# lightningbug.net
KiCad netlist of a schematic drawn in EAGLE
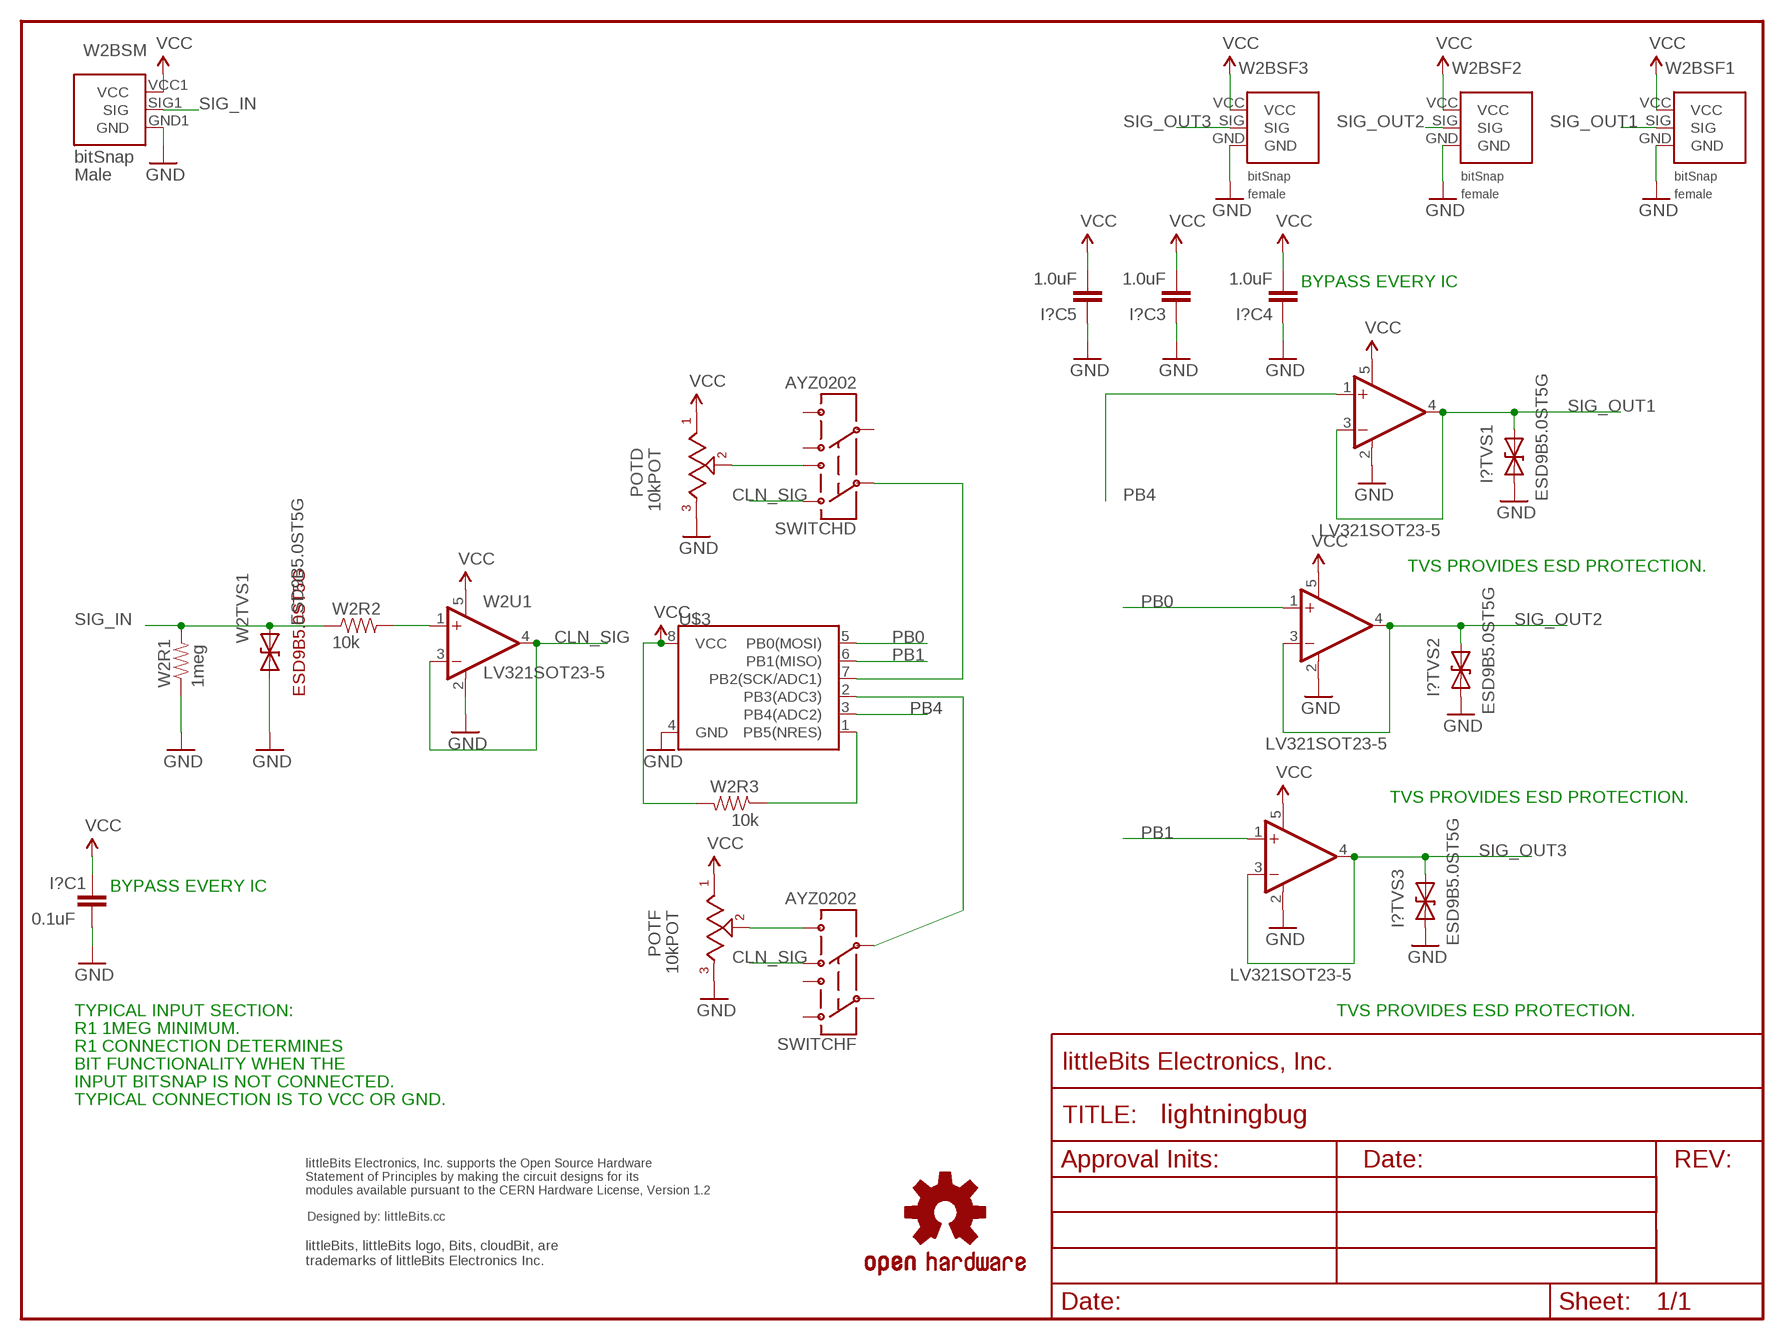
[diagram p0: schematic, sheet 1]

(export (version "E")
  (design (tool "Eeschema 10.0.6"))
  (components
    (comp (ref "FRAME1")
      (value "FRAME-LETTER")
      (footprint "eagle-import:FABDWG01-OHW")
      (libsource (lib "eagle-import") (part "FRAME-LETTER"))
    )
    (comp (ref "I?C1")
      (value "0.1uF")
      (footprint "eagle-import:CAP-0603")
      (libsource (lib "eagle-import") (part "CAPCAP-0603"))
    )
    (comp (ref "I?C3")
      (value "1.0uF")
      (footprint "eagle-import:CAP-0603")
      (libsource (lib "eagle-import") (part "CAPCAP-0603"))
    )
    (comp (ref "I?C4")
      (value "1.0uF")
      (footprint "eagle-import:CAP-0603")
      (libsource (lib "eagle-import") (part "CAPCAP-0603"))
    )
    (comp (ref "I?C5")
      (value "1.0uF")
      (footprint "eagle-import:CAP-0603")
      (libsource (lib "eagle-import") (part "CAPCAP-0603"))
    )
    (comp (ref "I?TVS1")
      (value "ESD9B5.0ST5G")
      (footprint "eagle-import:SOD-923")
      (libsource (lib "eagle-import") (part "DIODE-TVSSOD-923"))
    )
    (comp (ref "I?TVS2")
      (value "ESD9B5.0ST5G")
      (footprint "eagle-import:SOD-923")
      (libsource (lib "eagle-import") (part "DIODE-TVSSOD-923"))
    )
    (comp (ref "I?TVS3")
      (value "ESD9B5.0ST5G")
      (footprint "eagle-import:SOD-923")
      (libsource (lib "eagle-import") (part "DIODE-TVSSOD-923"))
    )
    (comp (ref "POTD")
      (value "10kPOT")
      (footprint "eagle-import:TRIMPOT_SMD_3MM")
      (libsource (lib "eagle-import") (part "TRIMPOT_SMD_3MM"))
    )
    (comp (ref "POTF")
      (value "10kPOT")
      (footprint "eagle-import:TRIMPOT_SMD_3MM")
      (libsource (lib "eagle-import") (part "TRIMPOT_SMD_3MM"))
    )
    (comp (ref "SWITCHD")
      (value "AYZ0202")
      (footprint "eagle-import:AYZ0202")
      (libsource (lib "eagle-import") (part "AYZ0202"))
    )
    (comp (ref "SWITCHF")
      (value "AYZ0202")
      (footprint "eagle-import:AYZ0202")
      (libsource (lib "eagle-import") (part "AYZ0202"))
    )
    (comp (ref "U$1")
      (value "OSHWCREDIT")
      (footprint "eagle-import:OSHWCREDIT")
      (libsource (lib "eagle-import") (part "OSHWCREDIT"))
    )
    (comp (ref "U$3")
      (value "ATTINY85")
      (footprint "eagle-import:SO08-EIAJ")
      (libsource (lib "eagle-import") (part "ATTINY85"))
    )
    (comp (ref "U$6")
      (value "OSHW-LOGOL")
      (footprint "eagle-import:OSHW-LOGO-L")
      (libsource (lib "eagle-import") (part "OSHW-LOGOL"))
    )
    (comp (ref "U1")
      (value "LV321SOT23-5")
      (footprint "eagle-import:SOT23-5")
      (libsource (lib "eagle-import") (part "LV321SOT23-5"))
    )
    (comp (ref "U2")
      (value "LV321SOT23-5")
      (footprint "eagle-import:SOT23-5")
      (libsource (lib "eagle-import") (part "LV321SOT23-5"))
    )
    (comp (ref "U3")
      (value "LV321SOT23-5")
      (footprint "eagle-import:SOT23-5")
      (libsource (lib "eagle-import") (part "LV321SOT23-5"))
    )
    (comp (ref "W2BSF1")
      (value "BITSNAP_V03_FEMALE")
      (footprint "eagle-import:BITSNAP_V03_FEMALE")
      (libsource (lib "eagle-import") (part "BITSNAP_V03_FEMALE"))
    )
    (comp (ref "W2BSF2")
      (value "BITSNAP_V03_FEMALE")
      (footprint "eagle-import:BITSNAP_V03_FEMALE")
      (libsource (lib "eagle-import") (part "BITSNAP_V03_FEMALE"))
    )
    (comp (ref "W2BSF3")
      (value "BITSNAP_V03_FEMALE")
      (footprint "eagle-import:BITSNAP_V03_FEMALE")
      (libsource (lib "eagle-import") (part "BITSNAP_V03_FEMALE"))
    )
    (comp (ref "W2BSM")
      (value "BITSNAP_V03_MALE")
      (footprint "eagle-import:BITSNAP_V03_MALE")
      (libsource (lib "eagle-import") (part "BITSNAP_V03_MALE"))
    )
    (comp (ref "W2R1")
      (value "1meg")
      (footprint "eagle-import:RES-0603")
      (libsource (lib "eagle-import") (part "RESISTOR0603"))
    )
    (comp (ref "W2R2")
      (value "10k")
      (footprint "eagle-import:RES-0603")
      (libsource (lib "eagle-import") (part "RESISTOR0603"))
    )
    (comp (ref "W2R3")
      (value "10k")
      (footprint "eagle-import:RES-0603")
      (libsource (lib "eagle-import") (part "RES-0603"))
    )
    (comp (ref "W2TVS1")
      (value "ESD9B5.0ST5G")
      (footprint "eagle-import:SOD-923")
      (libsource (lib "eagle-import") (part "DIODE-TVSSOD-923"))
    )
    (comp (ref "W2U1")
      (value "LV321SOT23-5")
      (footprint "eagle-import:SOT23-5")
      (libsource (lib "eagle-import") (part "LV321SOT23-5"))
    )
  )
  (nets
    (net (code "1") (name "/CLN_SIG") (class "Default")
      (node (ref "SWITCHD") (pin "1") (pinfunction "1_1") (pintype "bidirectional"))
      (node (ref "SWITCHF") (pin "4") (pinfunction "4_4") (pintype "bidirectional"))
      (node (ref "W2U1") (pin "3") (pinfunction "-IN_3") (pintype "input"))
      (node (ref "W2U1") (pin "4") (pinfunction "OUT_4") (pintype "output"))
    )
    (net (code "2") (name "/PB0") (class "Default")
      (node (ref "U$3") (pin "5") (pinfunction "PB0(MOSI)_5") (pintype "bidirectional"))
      (node (ref "U2") (pin "1") (pinfunction "+IN_1") (pintype "input"))
    )
    (net (code "3") (name "/PB1") (class "Default")
      (node (ref "U$3") (pin "6") (pinfunction "PB1(MISO)_6") (pintype "bidirectional"))
      (node (ref "U3") (pin "1") (pinfunction "+IN_1") (pintype "input"))
    )
    (net (code "4") (name "/PB4") (class "Default")
      (node (ref "U$3") (pin "3") (pinfunction "PB4(ADC2)_3") (pintype "bidirectional"))
      (node (ref "U1") (pin "1") (pinfunction "+IN_1") (pintype "input"))
    )
    (net (code "5") (name "/SIG_IN") (class "Default")
      (node (ref "W2BSM") (pin "SIG1") (pinfunction "SIG_SIG1") (pintype "bidirectional"))
      (node (ref "W2R1") (pin "2") (pinfunction "2_2") (pintype "passive"))
      (node (ref "W2R2") (pin "1") (pinfunction "1_1") (pintype "passive"))
      (node (ref "W2TVS1") (pin "2") (pinfunction "C_2") (pintype "passive"))
    )
    (net (code "6") (name "/SIG_OUT1") (class "Default")
      (node (ref "I?TVS1") (pin "2") (pinfunction "C_2") (pintype "passive"))
      (node (ref "U1") (pin "3") (pinfunction "-IN_3") (pintype "input"))
      (node (ref "U1") (pin "4") (pinfunction "OUT_4") (pintype "output"))
      (node (ref "W2BSF1") (pin "SIG") (pinfunction "SIG_SIG") (pintype "bidirectional"))
    )
    (net (code "7") (name "/SIG_OUT2") (class "Default")
      (node (ref "I?TVS2") (pin "2") (pinfunction "C_2") (pintype "passive"))
      (node (ref "U2") (pin "3") (pinfunction "-IN_3") (pintype "input"))
      (node (ref "U2") (pin "4") (pinfunction "OUT_4") (pintype "output"))
      (node (ref "W2BSF2") (pin "SIG") (pinfunction "SIG_SIG") (pintype "bidirectional"))
    )
    (net (code "8") (name "/SIG_OUT3") (class "Default")
      (node (ref "I?TVS3") (pin "2") (pinfunction "C_2") (pintype "passive"))
      (node (ref "U3") (pin "3") (pinfunction "-IN_3") (pintype "input"))
      (node (ref "U3") (pin "4") (pinfunction "OUT_4") (pintype "output"))
      (node (ref "W2BSF3") (pin "SIG") (pinfunction "SIG_SIG") (pintype "bidirectional"))
    )
    (net (code "9") (name "GND") (class "Default")
      (node (ref "I?C1") (pin "2") (pinfunction "2_2") (pintype "passive"))
      (node (ref "I?C3") (pin "1") (pinfunction "1_1") (pintype "passive"))
      (node (ref "I?C4") (pin "1") (pinfunction "1_1") (pintype "passive"))
      (node (ref "I?C5") (pin "1") (pinfunction "1_1") (pintype "passive"))
      (node (ref "I?TVS1") (pin "1") (pinfunction "A_1") (pintype "passive"))
      (node (ref "I?TVS2") (pin "1") (pinfunction "A_1") (pintype "passive"))
      (node (ref "I?TVS3") (pin "1") (pinfunction "A_1") (pintype "passive"))
      (node (ref "POTD") (pin "3") (pinfunction "3_3") (pintype "passive"))
      (node (ref "POTF") (pin "3") (pinfunction "3_3") (pintype "passive"))
      (node (ref "U$3") (pin "4") (pinfunction "GND_4") (pintype "bidirectional"))
      (node (ref "U1") (pin "2") (pinfunction "V-_2") (pintype "power_in"))
      (node (ref "U2") (pin "2") (pinfunction "V-_2") (pintype "power_in"))
      (node (ref "U3") (pin "2") (pinfunction "V-_2") (pintype "power_in"))
      (node (ref "W2BSF1") (pin "GND") (pinfunction "GND_GND") (pintype "bidirectional"))
      (node (ref "W2BSF2") (pin "GND") (pinfunction "GND_GND") (pintype "bidirectional"))
      (node (ref "W2BSF3") (pin "GND") (pinfunction "GND_GND") (pintype "bidirectional"))
      (node (ref "W2BSM") (pin "GND1") (pinfunction "GND_GND1") (pintype "bidirectional"))
      (node (ref "W2R1") (pin "1") (pinfunction "1_1") (pintype "passive"))
      (node (ref "W2TVS1") (pin "1") (pinfunction "A_1") (pintype "passive"))
      (node (ref "W2U1") (pin "2") (pinfunction "V-_2") (pintype "power_in"))
    )
    (net (code "10") (name "Net-(POTD-Pad2)") (class "Default")
      (node (ref "POTD") (pin "2") (pinfunction "2_2") (pintype "passive"))
      (node (ref "SWITCHD") (pin "3") (pinfunction "3_3") (pintype "bidirectional"))
    )
    (net (code "11") (name "Net-(POTF-Pad2)") (class "Default")
      (node (ref "POTF") (pin "2") (pinfunction "2_2") (pintype "passive"))
      (node (ref "SWITCHF") (pin "6") (pinfunction "6_6") (pintype "bidirectional"))
    )
    (net (code "12") (name "Net-(U$3-PB2(SCK{slash}ADC1))") (class "Default")
      (node (ref "SWITCHD") (pin "2") (pinfunction "2_2") (pintype "bidirectional"))
      (node (ref "U$3") (pin "7") (pinfunction "PB2(SCK/ADC1)_7") (pintype "bidirectional"))
    )
    (net (code "13") (name "Net-(U$3-PB3(ADC3))") (class "Default")
      (node (ref "SWITCHF") (pin "5") (pinfunction "5_5") (pintype "bidirectional"))
      (node (ref "U$3") (pin "2") (pinfunction "PB3(ADC3)_2") (pintype "bidirectional"))
    )
    (net (code "14") (name "Net-(U$3-PB5(NRES))") (class "Default")
      (node (ref "U$3") (pin "1") (pinfunction "PB5(NRES)_1") (pintype "bidirectional"))
      (node (ref "W2R3") (pin "1") (pinfunction "1_1") (pintype "passive"))
    )
    (net (code "15") (name "Net-(W2U1-+IN)") (class "Default")
      (node (ref "W2R2") (pin "2") (pinfunction "2_2") (pintype "passive"))
      (node (ref "W2U1") (pin "1") (pinfunction "+IN_1") (pintype "input"))
    )
    (net (code "16") (name "VCC") (class "Default")
      (node (ref "I?C1") (pin "1") (pinfunction "1_1") (pintype "passive"))
      (node (ref "I?C3") (pin "2") (pinfunction "2_2") (pintype "passive"))
      (node (ref "I?C4") (pin "2") (pinfunction "2_2") (pintype "passive"))
      (node (ref "I?C5") (pin "2") (pinfunction "2_2") (pintype "passive"))
      (node (ref "POTD") (pin "1") (pinfunction "1_1") (pintype "passive"))
      (node (ref "POTF") (pin "1") (pinfunction "1_1") (pintype "passive"))
      (node (ref "U$3") (pin "8") (pinfunction "VCC_8") (pintype "bidirectional"))
      (node (ref "U1") (pin "5") (pinfunction "V+_5") (pintype "power_in"))
      (node (ref "U2") (pin "5") (pinfunction "V+_5") (pintype "power_in"))
      (node (ref "U3") (pin "5") (pinfunction "V+_5") (pintype "power_in"))
      (node (ref "W2BSF1") (pin "VCC") (pinfunction "VCC_VCC") (pintype "bidirectional"))
      (node (ref "W2BSF2") (pin "VCC") (pinfunction "VCC_VCC") (pintype "bidirectional"))
      (node (ref "W2BSF3") (pin "VCC") (pinfunction "VCC_VCC") (pintype "bidirectional"))
      (node (ref "W2BSM") (pin "VCC1") (pinfunction "VCC_VCC1") (pintype "bidirectional"))
      (node (ref "W2R3") (pin "2") (pinfunction "2_2") (pintype "passive"))
      (node (ref "W2U1") (pin "5") (pinfunction "V+_5") (pintype "power_in"))
    )
    (net (code "17") (name "unconnected-(SWITCHD-Pad4)") (class "Default")
      (node (ref "SWITCHD") (pin "4") (pinfunction "4_4") (pintype "bidirectional"))
    )
    (net (code "18") (name "unconnected-(SWITCHD-Pad5)") (class "Default")
      (node (ref "SWITCHD") (pin "5") (pinfunction "5_5") (pintype "bidirectional"))
    )
    (net (code "19") (name "unconnected-(SWITCHD-Pad6)") (class "Default")
      (node (ref "SWITCHD") (pin "6") (pinfunction "6_6") (pintype "bidirectional"))
    )
    (net (code "20") (name "unconnected-(SWITCHF-Pad1)") (class "Default")
      (node (ref "SWITCHF") (pin "1") (pinfunction "1_1") (pintype "bidirectional"))
    )
    (net (code "21") (name "unconnected-(SWITCHF-Pad2)") (class "Default")
      (node (ref "SWITCHF") (pin "2") (pinfunction "2_2") (pintype "bidirectional"))
    )
    (net (code "22") (name "unconnected-(SWITCHF-Pad3)") (class "Default")
      (node (ref "SWITCHF") (pin "3") (pinfunction "3_3") (pintype "bidirectional"))
    )
  )
)
